# ServoBoard_342.net
KiCad netlist of a schematic drawn in Altium Designer
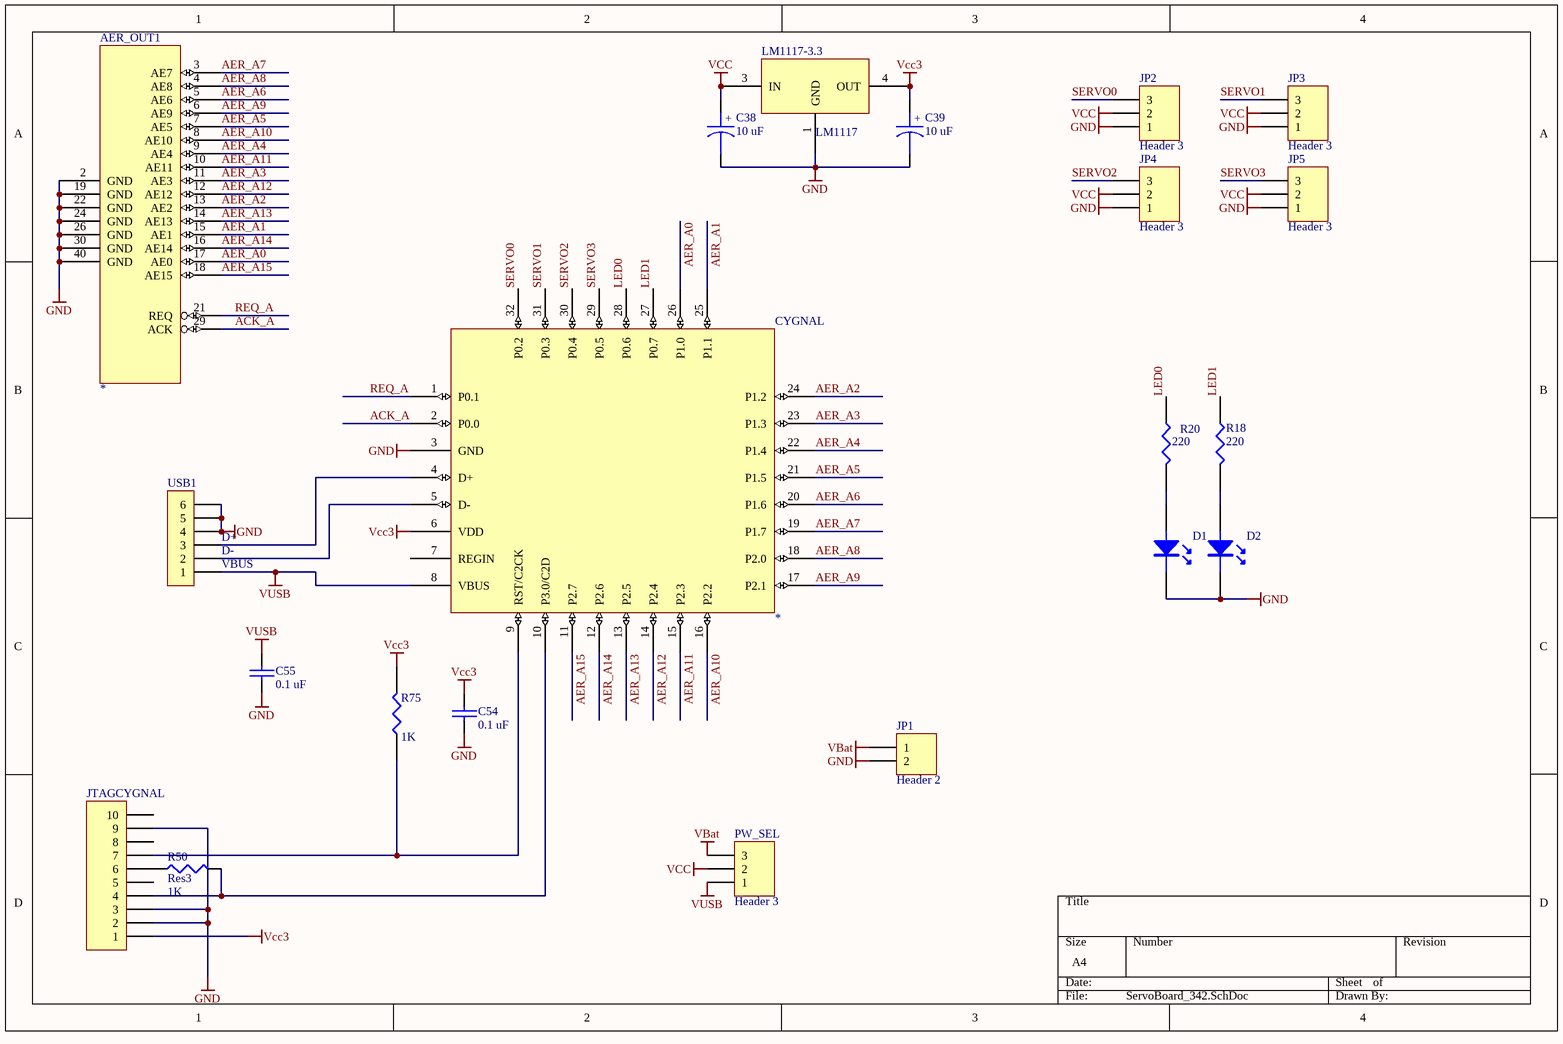
[diagram p0: ServoBoard_342.SchDoc]

(export (version "E")
  (design (tool "Eeschema 10.0.6"))
  (components
    (comp (ref "AER_OUT1") (value "*") (footprint "IDC-40") (libsource (lib "Schlib1") (part "CON_AER1")))
    (comp (ref "C38")
      (value "10 uF")
      (footprint "Minitantalo")
      (description "Capacitor")
      (libsource (lib "*") (part "CAPACITOR POL"))
    )
    (comp (ref "C39")
      (value "10 uF")
      (footprint "Minitantalo")
      (description "Capacitor")
      (libsource (lib "*") (part "CAPACITOR POL"))
    )
    (comp (ref "C54")
      (value "0.1 uF")
      (footprint "CAP 10")
      (description "Capacitor")
      (libsource (lib "*") (part "CAP"))
    )
    (comp (ref "C55")
      (value "0.1 uF")
      (footprint "CAP 10")
      (description "Capacitor")
      (libsource (lib "*") (part "CAP"))
    )
    (comp (ref "CYGNAL") (value "*") (footprint "LQFP-32") (libsource (lib "Schlib1") (part "C8051F320")))
    (comp (ref "D1") (value "~") (footprint "LED") (libsource (lib "*") (part "LED")))
    (comp (ref "D2") (value "~") (footprint "LED") (libsource (lib "*") (part "LED")))
    (comp (ref "JP1")
      (value "Header 2")
      (footprint "HDR1X2")
      (description "Header, 2-Pin")
      (fields (field (name "PUBLISHER") "Altium Limited"))
      (libsource (lib "Miscellaneous Connectors") (part "Header 2"))
    )
    (comp (ref "JP2")
      (value "Header 3")
      (footprint "HDR1X3")
      (description "Header, 3-Pin")
      (fields (field (name "PUBLISHER") "Altium Limited"))
      (libsource (lib "Miscellaneous Connectors") (part "Header 3"))
    )
    (comp (ref "JP3")
      (value "Header 3")
      (footprint "HDR1X3")
      (description "Header, 3-Pin")
      (fields (field (name "PUBLISHER") "Altium Limited"))
      (libsource (lib "Miscellaneous Connectors") (part "Header 3"))
    )
    (comp (ref "JP4")
      (value "Header 3")
      (footprint "HDR1X3")
      (description "Header, 3-Pin")
      (fields (field (name "PUBLISHER") "Altium Limited"))
      (libsource (lib "Miscellaneous Connectors") (part "Header 3"))
    )
    (comp (ref "JP5")
      (value "Header 3")
      (footprint "HDR1X3")
      (description "Header, 3-Pin")
      (fields (field (name "PUBLISHER") "Altium Limited"))
      (libsource (lib "Miscellaneous Connectors") (part "Header 3"))
    )
    (comp (ref "JTAGCYGNAL")
      (value "~")
      (footprint "IDC-10")
      (description "Connector")
      (libsource (lib "*") (part "CON10"))
    )
    (comp (ref "LM1117-3.3")
      (value "LM1117")
      (footprint "DSO-G3/D6.7")
      (libsource (lib "AD Voltage Reguilator") (part "LM1117"))
    )
    (comp (ref "PW_SEL")
      (value "Header 3")
      (footprint "HDR1X3")
      (description "Header, 3-Pin")
      (fields (field (name "PUBLISHER") "Altium Limited"))
      (libsource (lib "Miscellaneous Connectors") (part "Header 3"))
    )
    (comp (ref "R18") (value "220") (footprint "1608[0603]") (libsource (lib "*") (part "RES1")))
    (comp (ref "R20") (value "220") (footprint "1608[0603]") (libsource (lib "*") (part "RES1")))
    (comp (ref "R50")
      (value "Res3")
      (footprint "C1608-0603")
      (description "Resistor")
      (fields (field (name "ALTIUM_VALUE") "1K") (field (name "PUBLISHER") "Altium Limited"))
      (libsource (lib "Miscellaneous Devices") (part "Res3"))
    )
    (comp (ref "R75") (value "1K") (footprint "C1608-0603") (libsource (lib "*") (part "RES1")))
    (comp (ref "USB1")
      (value "~")
      (footprint "USB_CON")
      (description "Connector")
      (libsource (lib "*") (part "CON6"))
    )
  )
  (nets
    (net (code "1") (name "/ACK_A") (class "Default")
      (node (ref "AER_OUT1") (pin "29") (pinfunction "ACK_29") (pintype "bidirectional"))
      (node (ref "CYGNAL") (pin "2") (pinfunction "P0.0_2") (pintype "bidirectional"))
    )
    (net (code "2") (name "/AER_A0") (class "Default")
      (node (ref "AER_OUT1") (pin "17") (pinfunction "AE0_17") (pintype "bidirectional"))
      (node (ref "CYGNAL") (pin "26") (pinfunction "P1.0_26") (pintype "bidirectional"))
    )
    (net (code "3") (name "/AER_A1") (class "Default")
      (node (ref "AER_OUT1") (pin "15") (pinfunction "AE1_15") (pintype "bidirectional"))
      (node (ref "CYGNAL") (pin "25") (pinfunction "P1.1_25") (pintype "bidirectional"))
    )
    (net (code "4") (name "/AER_A2") (class "Default")
      (node (ref "AER_OUT1") (pin "13") (pinfunction "AE2_13") (pintype "bidirectional"))
      (node (ref "CYGNAL") (pin "24") (pinfunction "P1.2_24") (pintype "bidirectional"))
    )
    (net (code "5") (name "/AER_A3") (class "Default")
      (node (ref "AER_OUT1") (pin "11") (pinfunction "AE3_11") (pintype "bidirectional"))
      (node (ref "CYGNAL") (pin "23") (pinfunction "P1.3_23") (pintype "bidirectional"))
    )
    (net (code "6") (name "/AER_A4") (class "Default")
      (node (ref "AER_OUT1") (pin "9") (pinfunction "AE4_9") (pintype "bidirectional"))
      (node (ref "CYGNAL") (pin "22") (pinfunction "P1.4_22") (pintype "bidirectional"))
    )
    (net (code "7") (name "/AER_A5") (class "Default")
      (node (ref "AER_OUT1") (pin "7") (pinfunction "AE5_7") (pintype "bidirectional"))
      (node (ref "CYGNAL") (pin "21") (pinfunction "P1.5_21") (pintype "bidirectional"))
    )
    (net (code "8") (name "/AER_A6") (class "Default")
      (node (ref "AER_OUT1") (pin "5") (pinfunction "AE6_5") (pintype "bidirectional"))
      (node (ref "CYGNAL") (pin "20") (pinfunction "P1.6_20") (pintype "bidirectional"))
    )
    (net (code "9") (name "/AER_A7") (class "Default")
      (node (ref "AER_OUT1") (pin "3") (pinfunction "AE7_3") (pintype "bidirectional"))
      (node (ref "CYGNAL") (pin "19") (pinfunction "P1.7_19") (pintype "bidirectional"))
    )
    (net (code "10") (name "/AER_A8") (class "Default")
      (node (ref "AER_OUT1") (pin "4") (pinfunction "AE8_4") (pintype "bidirectional"))
      (node (ref "CYGNAL") (pin "18") (pinfunction "P2.0_18") (pintype "bidirectional"))
    )
    (net (code "11") (name "/AER_A9") (class "Default")
      (node (ref "AER_OUT1") (pin "6") (pinfunction "AE9_6") (pintype "bidirectional"))
      (node (ref "CYGNAL") (pin "17") (pinfunction "P2.1_17") (pintype "bidirectional"))
    )
    (net (code "12") (name "/AER_A10") (class "Default")
      (node (ref "AER_OUT1") (pin "8") (pinfunction "AE10_8") (pintype "bidirectional"))
      (node (ref "CYGNAL") (pin "16") (pinfunction "P2.2_16") (pintype "bidirectional"))
    )
    (net (code "13") (name "/AER_A11") (class "Default")
      (node (ref "AER_OUT1") (pin "10") (pinfunction "AE11_10") (pintype "bidirectional"))
      (node (ref "CYGNAL") (pin "15") (pinfunction "P2.3_15") (pintype "bidirectional"))
    )
    (net (code "14") (name "/AER_A12") (class "Default")
      (node (ref "AER_OUT1") (pin "12") (pinfunction "AE12_12") (pintype "bidirectional"))
      (node (ref "CYGNAL") (pin "14") (pinfunction "P2.4_14") (pintype "bidirectional"))
    )
    (net (code "15") (name "/AER_A13") (class "Default")
      (node (ref "AER_OUT1") (pin "14") (pinfunction "AE13_14") (pintype "bidirectional"))
      (node (ref "CYGNAL") (pin "13") (pinfunction "P2.5_13") (pintype "bidirectional"))
    )
    (net (code "16") (name "/AER_A14") (class "Default")
      (node (ref "AER_OUT1") (pin "16") (pinfunction "AE14_16") (pintype "bidirectional"))
      (node (ref "CYGNAL") (pin "12") (pinfunction "P2.6_12") (pintype "bidirectional"))
    )
    (net (code "17") (name "/AER_A15") (class "Default")
      (node (ref "AER_OUT1") (pin "18") (pinfunction "AE15_18") (pintype "bidirectional"))
      (node (ref "CYGNAL") (pin "11") (pinfunction "P2.7_11") (pintype "bidirectional"))
    )
    (net (code "18") (name "/LED0") (class "Default")
      (node (ref "CYGNAL") (pin "28") (pinfunction "P0.6_28") (pintype "bidirectional"))
      (node (ref "R20") (pin "1") (pinfunction "1_1") (pintype "passive"))
    )
    (net (code "19") (name "/LED1") (class "Default")
      (node (ref "CYGNAL") (pin "27") (pinfunction "P0.7_27") (pintype "bidirectional"))
      (node (ref "R18") (pin "1") (pinfunction "1_1") (pintype "passive"))
    )
    (net (code "20") (name "/REQ_A") (class "Default")
      (node (ref "AER_OUT1") (pin "21") (pinfunction "REQ_21") (pintype "bidirectional"))
      (node (ref "CYGNAL") (pin "1") (pinfunction "P0.1_1") (pintype "bidirectional"))
    )
    (net (code "21") (name "/SERVO0") (class "Default")
      (node (ref "CYGNAL") (pin "32") (pinfunction "P0.2_32") (pintype "bidirectional"))
      (node (ref "JP2") (pin "3") (pinfunction "3_3") (pintype "passive"))
    )
    (net (code "22") (name "/SERVO1") (class "Default")
      (node (ref "CYGNAL") (pin "31") (pinfunction "P0.3_31") (pintype "bidirectional"))
      (node (ref "JP3") (pin "3") (pinfunction "3_3") (pintype "passive"))
    )
    (net (code "23") (name "/SERVO2") (class "Default")
      (node (ref "CYGNAL") (pin "30") (pinfunction "P0.4_30") (pintype "bidirectional"))
      (node (ref "JP4") (pin "3") (pinfunction "3_3") (pintype "passive"))
    )
    (net (code "24") (name "/SERVO3") (class "Default")
      (node (ref "CYGNAL") (pin "29") (pinfunction "P0.5_29") (pintype "bidirectional"))
      (node (ref "JP5") (pin "3") (pinfunction "3_3") (pintype "passive"))
    )
    (net (code "25") (name "GND") (class "Default")
      (node (ref "AER_OUT1") (pin "19") (pinfunction "GND_19") (pintype "power_in"))
      (node (ref "AER_OUT1") (pin "2") (pinfunction "GND_2") (pintype "power_in"))
      (node (ref "AER_OUT1") (pin "22") (pinfunction "GND_22") (pintype "power_in"))
      (node (ref "AER_OUT1") (pin "24") (pinfunction "GND_24") (pintype "power_in"))
      (node (ref "AER_OUT1") (pin "26") (pinfunction "GND_26") (pintype "power_in"))
      (node (ref "AER_OUT1") (pin "30") (pinfunction "GND_30") (pintype "power_in"))
      (node (ref "AER_OUT1") (pin "40") (pinfunction "GND_40") (pintype "power_in"))
      (node (ref "C38") (pin "2") (pinfunction "2_2") (pintype "passive"))
      (node (ref "C39") (pin "2") (pinfunction "2_2") (pintype "passive"))
      (node (ref "C54") (pin "2") (pinfunction "2_2") (pintype "passive"))
      (node (ref "C55") (pin "2") (pinfunction "2_2") (pintype "passive"))
      (node (ref "CYGNAL") (pin "3") (pinfunction "GND_3") (pintype "power_in"))
      (node (ref "D1") (pin "K") (pinfunction "2_K") (pintype "passive"))
      (node (ref "D2") (pin "K") (pinfunction "2_K") (pintype "passive"))
      (node (ref "JP1") (pin "2") (pinfunction "2_2") (pintype "passive"))
      (node (ref "JP2") (pin "1") (pinfunction "1_1") (pintype "passive"))
      (node (ref "JP3") (pin "1") (pinfunction "1_1") (pintype "passive"))
      (node (ref "JP4") (pin "1") (pinfunction "1_1") (pintype "passive"))
      (node (ref "JP5") (pin "1") (pinfunction "1_1") (pintype "passive"))
      (node (ref "JTAGCYGNAL") (pin "2") (pinfunction "2_2") (pintype "passive"))
      (node (ref "JTAGCYGNAL") (pin "3") (pinfunction "3_3") (pintype "passive"))
      (node (ref "JTAGCYGNAL") (pin "9") (pinfunction "9_9") (pintype "passive"))
      (node (ref "LM1117-3.3") (pin "1") (pinfunction "GND_1") (pintype "power_in"))
      (node (ref "USB1") (pin "4") (pinfunction "4_4") (pintype "passive"))
      (node (ref "USB1") (pin "5") (pinfunction "5_5") (pintype "passive"))
      (node (ref "USB1") (pin "6") (pinfunction "6_6") (pintype "passive"))
    )
    (net (code "26") (name "Net-(CYGNAL-D+)") (class "Default")
      (node (ref "CYGNAL") (pin "4") (pinfunction "D+_4") (pintype "bidirectional"))
      (node (ref "USB1") (pin "3") (pinfunction "3_3") (pintype "passive"))
    )
    (net (code "27") (name "Net-(CYGNAL-D-)") (class "Default")
      (node (ref "CYGNAL") (pin "5") (pinfunction "D-_5") (pintype "bidirectional"))
      (node (ref "USB1") (pin "2") (pinfunction "2_2") (pintype "passive"))
    )
    (net (code "28") (name "Net-(CYGNAL-P3.0{slash}C2D)") (class "Default")
      (node (ref "CYGNAL") (pin "10") (pinfunction "P3.0/C2D_10") (pintype "bidirectional"))
      (node (ref "JTAGCYGNAL") (pin "4") (pinfunction "4_4") (pintype "passive"))
      (node (ref "R50") (pin "2") (pinfunction "2_2") (pintype "passive"))
    )
    (net (code "29") (name "Net-(CYGNAL-RST{slash}C2CK)") (class "Default")
      (node (ref "CYGNAL") (pin "9") (pinfunction "RST/C2CK_9") (pintype "bidirectional"))
      (node (ref "JTAGCYGNAL") (pin "7") (pinfunction "7_7") (pintype "passive"))
      (node (ref "R75") (pin "1") (pinfunction "1_1") (pintype "passive"))
    )
    (net (code "30") (name "Net-(D1-1)") (class "Default")
      (node (ref "D1") (pin "A") (pinfunction "1_A") (pintype "passive"))
      (node (ref "R20") (pin "2") (pinfunction "2_2") (pintype "passive"))
    )
    (net (code "31") (name "Net-(D2-1)") (class "Default")
      (node (ref "D2") (pin "A") (pinfunction "1_A") (pintype "passive"))
      (node (ref "R18") (pin "2") (pinfunction "2_2") (pintype "passive"))
    )
    (net (code "32") (name "Net-(JTAGCYGNAL-Pad6)") (class "Default")
      (node (ref "JTAGCYGNAL") (pin "6") (pinfunction "6_6") (pintype "passive"))
      (node (ref "R50") (pin "1") (pinfunction "1_1") (pintype "passive"))
    )
    (net (code "33") (name "VBat") (class "Default")
      (node (ref "JP1") (pin "1") (pinfunction "1_1") (pintype "passive"))
      (node (ref "PW_SEL") (pin "3") (pinfunction "3_3") (pintype "passive"))
    )
    (net (code "34") (name "VCC") (class "Default")
      (node (ref "C38") (pin "1") (pinfunction "1_1") (pintype "passive"))
      (node (ref "JP2") (pin "2") (pinfunction "2_2") (pintype "passive"))
      (node (ref "JP3") (pin "2") (pinfunction "2_2") (pintype "passive"))
      (node (ref "JP4") (pin "2") (pinfunction "2_2") (pintype "passive"))
      (node (ref "JP5") (pin "2") (pinfunction "2_2") (pintype "passive"))
      (node (ref "LM1117-3.3") (pin "3") (pinfunction "IN_3") (pintype "power_in"))
      (node (ref "PW_SEL") (pin "2") (pinfunction "2_2") (pintype "passive"))
    )
    (net (code "35") (name "VUSB") (class "Default")
      (node (ref "C55") (pin "1") (pinfunction "1_1") (pintype "passive"))
      (node (ref "CYGNAL") (pin "8") (pinfunction "VBUS_8") (pintype "power_in"))
      (node (ref "PW_SEL") (pin "1") (pinfunction "1_1") (pintype "passive"))
      (node (ref "USB1") (pin "1") (pinfunction "1_1") (pintype "passive"))
    )
    (net (code "36") (name "Vcc3") (class "Default")
      (node (ref "C39") (pin "1") (pinfunction "1_1") (pintype "passive"))
      (node (ref "C54") (pin "1") (pinfunction "1_1") (pintype "passive"))
      (node (ref "CYGNAL") (pin "6") (pinfunction "VDD_6") (pintype "power_in"))
      (node (ref "JTAGCYGNAL") (pin "1") (pinfunction "1_1") (pintype "passive"))
      (node (ref "LM1117-3.3") (pin "4") (pinfunction "OUT_4") (pintype "power_in"))
      (node (ref "R75") (pin "2") (pinfunction "2_2") (pintype "passive"))
    )
    (net (code "37") (name "unconnected-(CYGNAL-REGIN-Pad7)") (class "Default")
      (node (ref "CYGNAL") (pin "7") (pinfunction "REGIN_7") (pintype "power_in"))
    )
    (net (code "38") (name "unconnected-(JTAGCYGNAL-Pad5)") (class "Default")
      (node (ref "JTAGCYGNAL") (pin "5") (pinfunction "5_5") (pintype "passive"))
    )
    (net (code "39") (name "unconnected-(JTAGCYGNAL-Pad8)") (class "Default")
      (node (ref "JTAGCYGNAL") (pin "8") (pinfunction "8_8") (pintype "passive"))
    )
    (net (code "40") (name "unconnected-(JTAGCYGNAL-Pad10)") (class "Default")
      (node (ref "JTAGCYGNAL") (pin "10") (pinfunction "10_10") (pintype "passive"))
    )
  )
)
